# main.net
KiCad netlist of a schematic drawn in EAGLE
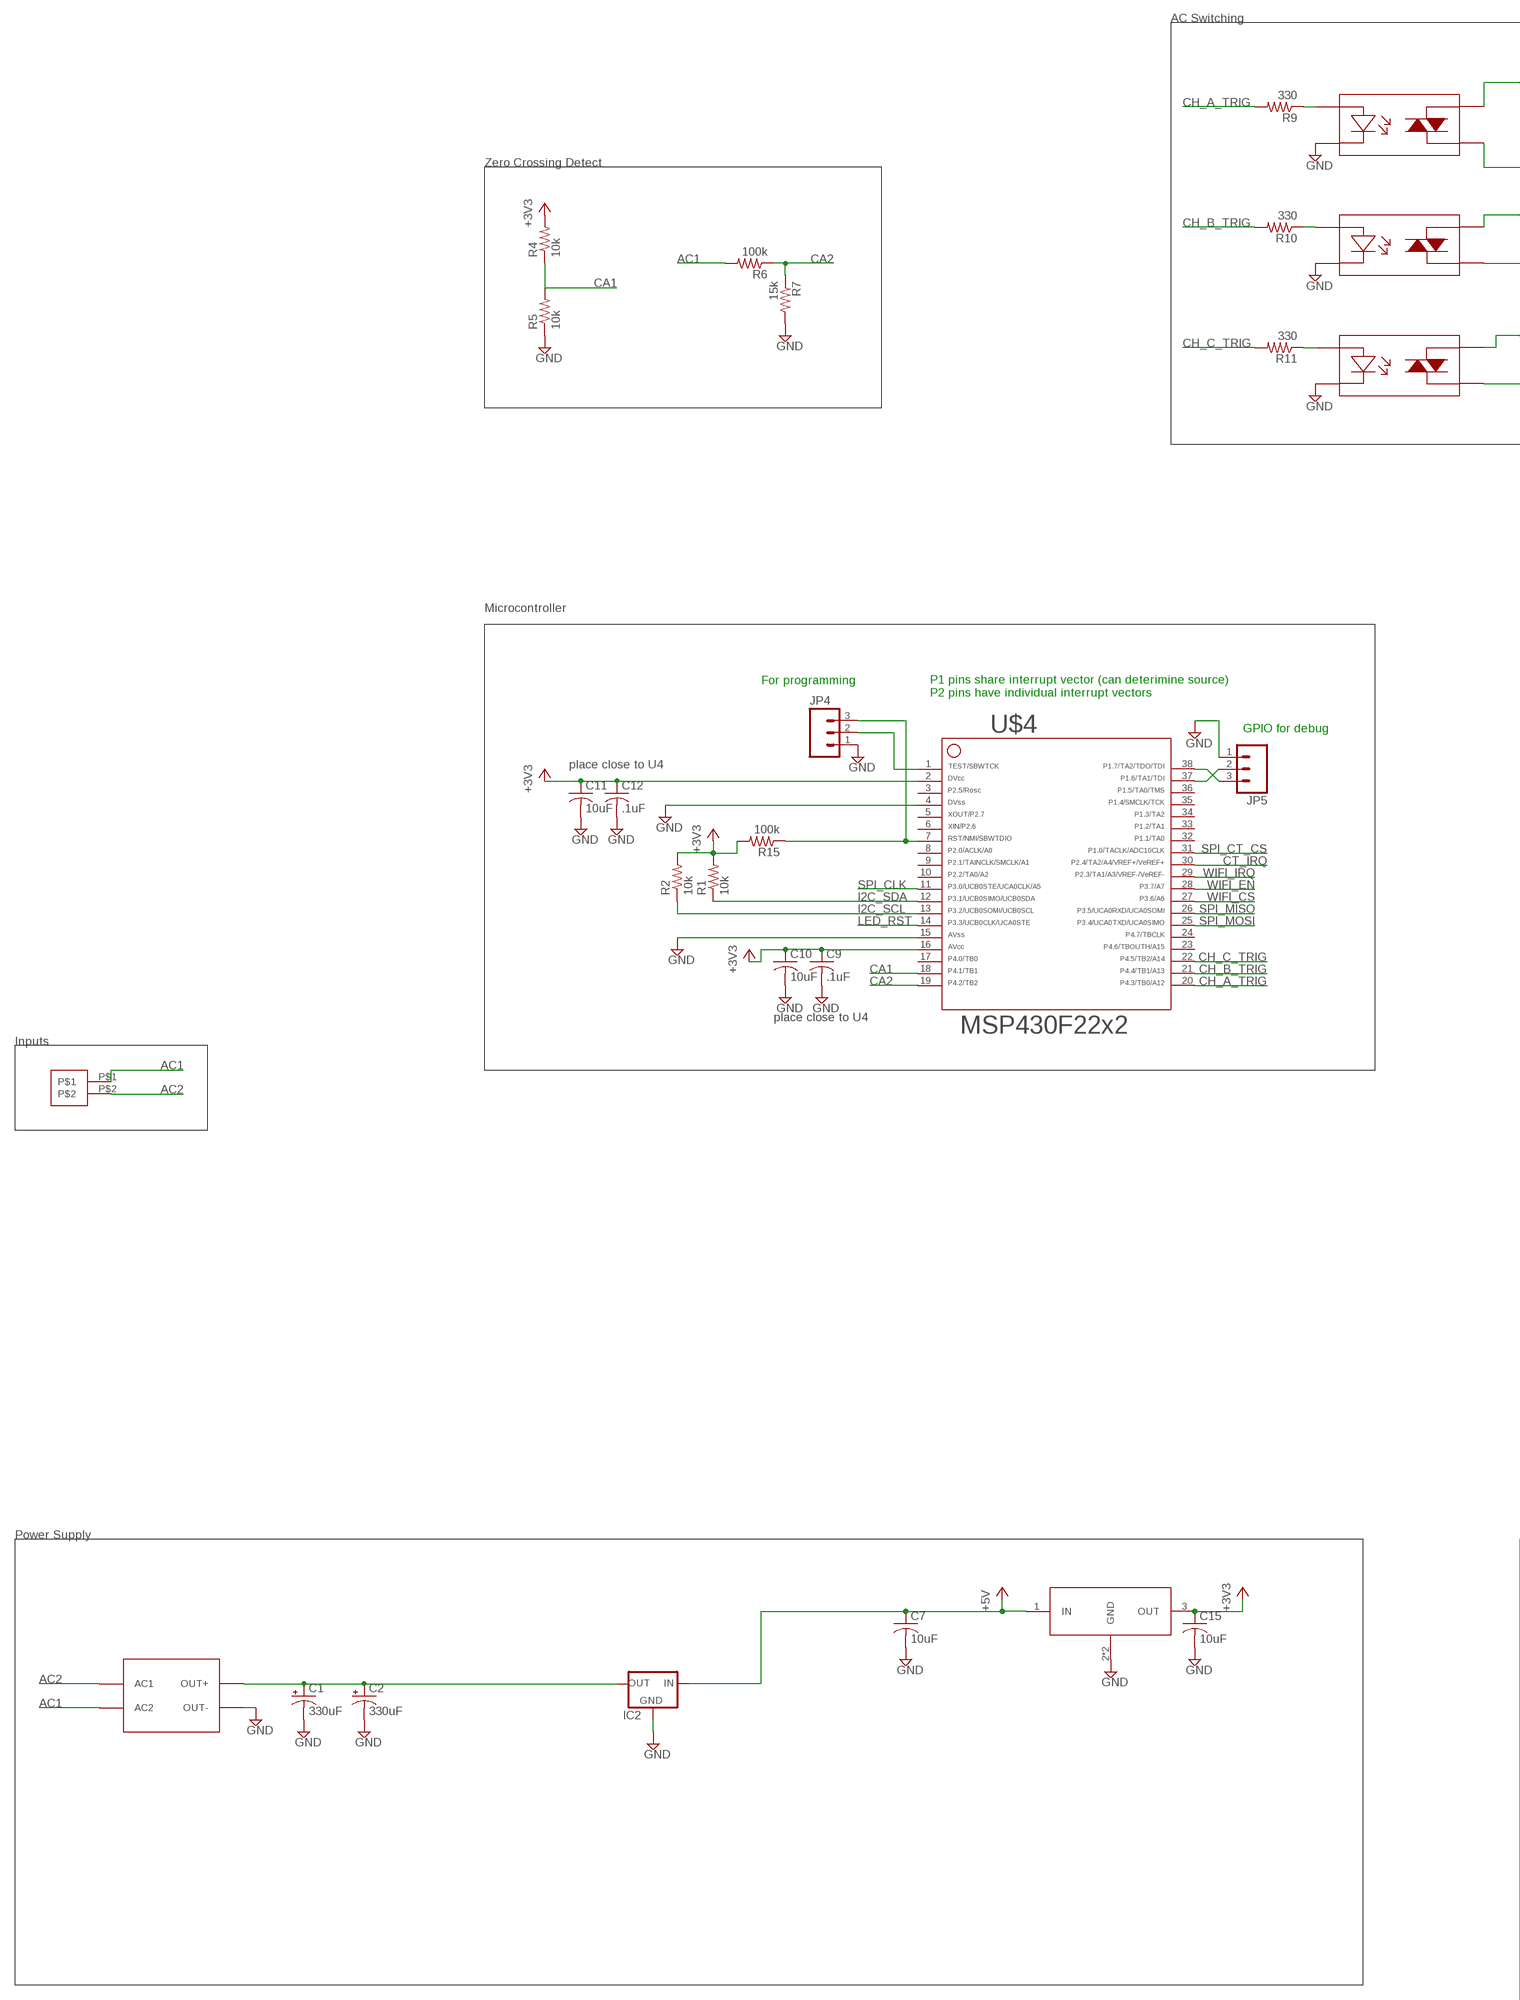
[diagram p0: schematic, sheet 1, part 1 of 2]
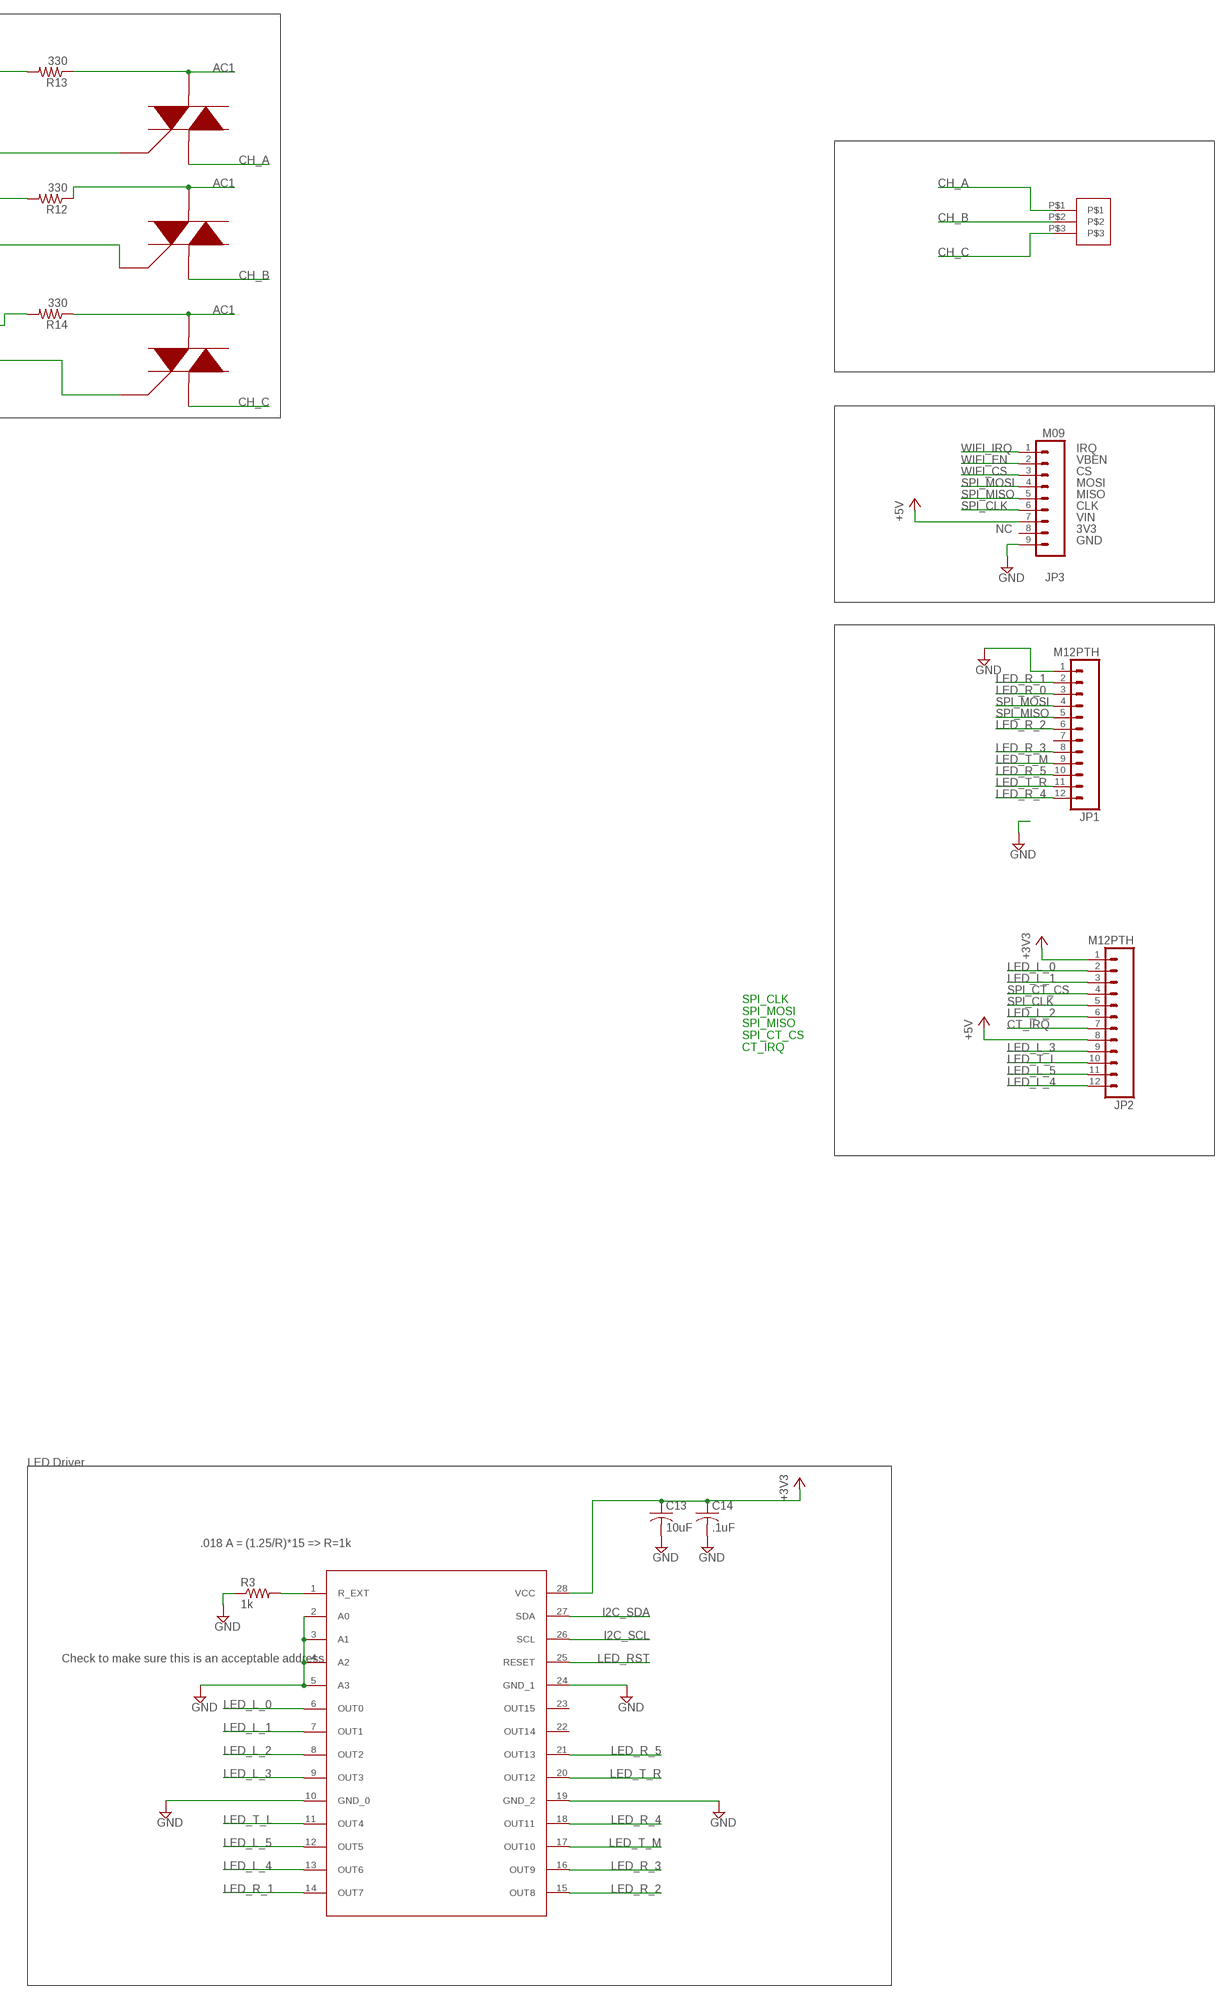
[diagram p1: schematic, sheet 1, part 2 of 2]

(export (version "E")
  (design (tool "Eeschema 10.0.6"))
  (components
    (comp (ref "C1")
      (value "330uF")
      (footprint "eagle-import:RADIAL_CAN_SMD")
      (libsource (lib "eagle-import") (part "EEE-1VA331UAP"))
    )
    (comp (ref "C2")
      (value "330uF")
      (footprint "eagle-import:RADIAL_CAN_SMD")
      (libsource (lib "eagle-import") (part "EEE-1VA331UAP"))
    )
    (comp (ref "C7")
      (value "10uF")
      (footprint "eagle-import:C0603K")
      (libsource (lib "eagle-import") (part "C-USC0603K"))
    )
    (comp (ref "C9")
      (value ".1uF")
      (footprint "eagle-import:C0603K")
      (libsource (lib "eagle-import") (part "C-USC0603K"))
    )
    (comp (ref "C10")
      (value "10uF")
      (footprint "eagle-import:C0603K")
      (libsource (lib "eagle-import") (part "C-USC0603K"))
    )
    (comp (ref "C11")
      (value "10uF")
      (footprint "eagle-import:C0603K")
      (libsource (lib "eagle-import") (part "C-USC0603K"))
    )
    (comp (ref "C12")
      (value ".1uF")
      (footprint "eagle-import:C0603K")
      (libsource (lib "eagle-import") (part "C-USC0603K"))
    )
    (comp (ref "C13")
      (value "10uF")
      (footprint "eagle-import:C0603K")
      (libsource (lib "eagle-import") (part "C-USC0603K"))
    )
    (comp (ref "C14")
      (value ".1uF")
      (footprint "eagle-import:C0603K")
      (libsource (lib "eagle-import") (part "C-USC0603K"))
    )
    (comp (ref "C15")
      (value "10uF")
      (footprint "eagle-import:C0603K")
      (libsource (lib "eagle-import") (part "C-USC0603K"))
    )
    (comp (ref "IC2")
      (value "V_REG_78XX-TO-220")
      (footprint "eagle-import:TO-220-ALT")
      (libsource (lib "eagle-import") (part "V_REG_78XX-TO-220"))
    )
    (comp (ref "J1")
      (value "3-1437646-3")
      (footprint "eagle-import:3-1437646-3")
      (libsource (lib "eagle-import") (part "3-1437646-3"))
    )
    (comp (ref "J2")
      (value "3-1437646-9")
      (footprint "eagle-import:3-1437646-9")
      (libsource (lib "eagle-import") (part "3-1437646-9"))
    )
    (comp (ref "JP1")
      (value "M12PTH")
      (footprint "eagle-import:1X12")
      (libsource (lib "eagle-import") (part "M12PTH"))
    )
    (comp (ref "JP2")
      (value "M12PTH")
      (footprint "eagle-import:1X12")
      (libsource (lib "eagle-import") (part "M12PTH"))
    )
    (comp (ref "JP3")
      (value "M09")
      (footprint "eagle-import:1X09")
      (libsource (lib "eagle-import") (part "M09"))
    )
    (comp (ref "JP4")
      (value "M03PTH")
      (footprint "eagle-import:1X03")
      (libsource (lib "eagle-import") (part "M03PTH"))
    )
    (comp (ref "JP5")
      (value "M03PTH")
      (footprint "eagle-import:1X03")
      (libsource (lib "eagle-import") (part "M03PTH"))
    )
    (comp (ref "R1")
      (value "10k")
      (footprint "eagle-import:R0603")
      (libsource (lib "eagle-import") (part "R-US_R0603"))
    )
    (comp (ref "R2")
      (value "10k")
      (footprint "eagle-import:R0603")
      (libsource (lib "eagle-import") (part "R-US_R0603"))
    )
    (comp (ref "R3")
      (value "1k")
      (footprint "eagle-import:R0603")
      (libsource (lib "eagle-import") (part "R-US_R0603"))
    )
    (comp (ref "R4")
      (value "10k")
      (footprint "eagle-import:R0603")
      (libsource (lib "eagle-import") (part "R-US_R0603"))
    )
    (comp (ref "R5")
      (value "10k")
      (footprint "eagle-import:R0603")
      (libsource (lib "eagle-import") (part "R-US_R0603"))
    )
    (comp (ref "R6")
      (value "100k")
      (footprint "eagle-import:R0603")
      (libsource (lib "eagle-import") (part "R-US_R0603"))
    )
    (comp (ref "R7")
      (value "15k")
      (footprint "eagle-import:R0603")
      (libsource (lib "eagle-import") (part "R-US_R0603"))
    )
    (comp (ref "R9")
      (value "330")
      (footprint "eagle-import:R0603")
      (libsource (lib "eagle-import") (part "R-US_R0603"))
    )
    (comp (ref "R10")
      (value "330")
      (footprint "eagle-import:R0603")
      (libsource (lib "eagle-import") (part "R-US_R0603"))
    )
    (comp (ref "R11")
      (value "330")
      (footprint "eagle-import:R0603")
      (libsource (lib "eagle-import") (part "R-US_R0603"))
    )
    (comp (ref "R12")
      (value "330")
      (footprint "eagle-import:R0603")
      (libsource (lib "eagle-import") (part "R-US_R0603"))
    )
    (comp (ref "R13")
      (value "330")
      (footprint "eagle-import:R0603")
      (libsource (lib "eagle-import") (part "R-US_R0603"))
    )
    (comp (ref "R14")
      (value "330")
      (footprint "eagle-import:R0603")
      (libsource (lib "eagle-import") (part "R-US_R0603"))
    )
    (comp (ref "R15")
      (value "100k")
      (footprint "eagle-import:R0603")
      (libsource (lib "eagle-import") (part "R-US_R0603"))
    )
    (comp (ref "U$1")
      (value "FODM3011")
      (footprint "eagle-import:SMD-4")
      (libsource (lib "eagle-import") (part "FODM3011"))
    )
    (comp (ref "U$2")
      (value "DS1501S-T")
      (footprint "eagle-import:DF-S")
      (libsource (lib "eagle-import") (part "DS1501S-T"))
    )
    (comp (ref "U$3")
      (value "TLC59116")
      (footprint "eagle-import:PW_28")
      (libsource (lib "eagle-import") (part "TLC59116"))
    )
    (comp (ref "U$4")
      (value "F22X2---DA38")
      (footprint "eagle-import:DA38")
      (libsource (lib "eagle-import") (part "F22X2---DA38"))
    )
    (comp (ref "U$5")
      (value "LM2937")
      (footprint "eagle-import:SOT223")
      (libsource (lib "eagle-import") (part "LM2937"))
    )
    (comp (ref "U$6")
      (value "FODM3011")
      (footprint "eagle-import:SMD-4")
      (libsource (lib "eagle-import") (part "FODM3011"))
    )
    (comp (ref "U$7")
      (value "FODM3011")
      (footprint "eagle-import:SMD-4")
      (libsource (lib "eagle-import") (part "FODM3011"))
    )
    (comp (ref "U$9")
      (value "BT-137S-600D")
      (footprint "eagle-import:SOT428")
      (libsource (lib "eagle-import") (part "BT-137S-600D"))
    )
    (comp (ref "U$10")
      (value "BT-137S-600D")
      (footprint "eagle-import:SOT428")
      (libsource (lib "eagle-import") (part "BT-137S-600D"))
    )
    (comp (ref "U$11")
      (value "BT-137S-600D")
      (footprint "eagle-import:SOT428")
      (libsource (lib "eagle-import") (part "BT-137S-600D"))
    )
  )
  (nets
    (net (code "1") (name "+3V3") (class "Default")
      (node (ref "C10") (pin "1") (pinfunction "1_1") (pintype "passive"))
      (node (ref "C11") (pin "1") (pinfunction "1_1") (pintype "passive"))
      (node (ref "C12") (pin "1") (pinfunction "1_1") (pintype "passive"))
      (node (ref "C13") (pin "1") (pinfunction "1_1") (pintype "passive"))
      (node (ref "C14") (pin "1") (pinfunction "1_1") (pintype "passive"))
      (node (ref "C15") (pin "1") (pinfunction "1_1") (pintype "passive"))
      (node (ref "C9") (pin "1") (pinfunction "1_1") (pintype "passive"))
      (node (ref "JP2") (pin "1") (pinfunction "1_1") (pintype "passive"))
      (node (ref "R1") (pin "2") (pinfunction "2_2") (pintype "passive"))
      (node (ref "R15") (pin "2") (pinfunction "2_2") (pintype "passive"))
      (node (ref "R2") (pin "2") (pinfunction "2_2") (pintype "passive"))
      (node (ref "R4") (pin "2") (pinfunction "2_2") (pintype "passive"))
      (node (ref "U$3") (pin "28") (pinfunction "VCC_28") (pintype "bidirectional"))
      (node (ref "U$4") (pin "16") (pinfunction "16_16") (pintype "power_in"))
      (node (ref "U$4") (pin "2") (pinfunction "2_2") (pintype "power_in"))
      (node (ref "U$5") (pin "3") (pinfunction "OUT_3") (pintype "bidirectional"))
    )
    (net (code "2") (name "+5V") (class "Default")
      (node (ref "C7") (pin "1") (pinfunction "1_1") (pintype "passive"))
      (node (ref "IC2") (pin "IN") (pinfunction "IN_IN") (pintype "input"))
      (node (ref "JP2") (pin "8") (pinfunction "8_8") (pintype "passive"))
      (node (ref "JP3") (pin "7") (pinfunction "7_7") (pintype "passive"))
      (node (ref "U$5") (pin "1") (pinfunction "IN_1") (pintype "bidirectional"))
    )
    (net (code "3") (name "/AC1") (class "Default")
      (node (ref "J1") (pin "P$1") (pinfunction "P$1_P$1") (pintype "bidirectional"))
      (node (ref "R12") (pin "1") (pinfunction "1_1") (pintype "passive"))
      (node (ref "R13") (pin "1") (pinfunction "1_1") (pintype "passive"))
      (node (ref "R14") (pin "1") (pinfunction "1_1") (pintype "passive"))
      (node (ref "R6") (pin "2") (pinfunction "2_2") (pintype "passive"))
      (node (ref "U$10") (pin "T2") (pinfunction "S2_T2") (pintype "bidirectional"))
      (node (ref "U$11") (pin "T2") (pinfunction "S2_T2") (pintype "bidirectional"))
      (node (ref "U$2") (pin "P$4") (pinfunction "AC2_P$4") (pintype "bidirectional"))
      (node (ref "U$9") (pin "T2") (pinfunction "S2_T2") (pintype "bidirectional"))
    )
    (net (code "4") (name "/AC2") (class "Default")
      (node (ref "J1") (pin "P$2") (pinfunction "P$2_P$2") (pintype "bidirectional"))
      (node (ref "U$2") (pin "P$3") (pinfunction "AC1_P$3") (pintype "bidirectional"))
    )
    (net (code "5") (name "/CA1") (class "Default")
      (node (ref "R4") (pin "1") (pinfunction "1_1") (pintype "passive"))
      (node (ref "R5") (pin "2") (pinfunction "2_2") (pintype "passive"))
      (node (ref "U$4") (pin "18") (pinfunction "18_18") (pintype "bidirectional"))
    )
    (net (code "6") (name "/CA2") (class "Default")
      (node (ref "R6") (pin "1") (pinfunction "1_1") (pintype "passive"))
      (node (ref "R7") (pin "1") (pinfunction "1_1") (pintype "passive"))
      (node (ref "U$4") (pin "19") (pinfunction "19_19") (pintype "bidirectional"))
    )
    (net (code "7") (name "/CH_A") (class "Default")
      (node (ref "J2") (pin "P$1") (pinfunction "P$1_P$1") (pintype "bidirectional"))
      (node (ref "U$9") (pin "T1") (pinfunction "S1_T1") (pintype "bidirectional"))
    )
    (net (code "8") (name "/CH_A_TRIG") (class "Default")
      (node (ref "R9") (pin "2") (pinfunction "2_2") (pintype "passive"))
      (node (ref "U$4") (pin "20") (pinfunction "20_20") (pintype "bidirectional"))
    )
    (net (code "9") (name "/CH_B") (class "Default")
      (node (ref "J2") (pin "P$2") (pinfunction "P$2_P$2") (pintype "bidirectional"))
      (node (ref "U$10") (pin "T1") (pinfunction "S1_T1") (pintype "bidirectional"))
    )
    (net (code "10") (name "/CH_B_TRIG") (class "Default")
      (node (ref "R10") (pin "2") (pinfunction "2_2") (pintype "passive"))
      (node (ref "U$4") (pin "21") (pinfunction "21_21") (pintype "bidirectional"))
    )
    (net (code "11") (name "/CH_C") (class "Default")
      (node (ref "J2") (pin "P$3") (pinfunction "P$3_P$3") (pintype "bidirectional"))
      (node (ref "U$11") (pin "T1") (pinfunction "S1_T1") (pintype "bidirectional"))
    )
    (net (code "12") (name "/CH_C_TRIG") (class "Default")
      (node (ref "R11") (pin "2") (pinfunction "2_2") (pintype "passive"))
      (node (ref "U$4") (pin "22") (pinfunction "22_22") (pintype "bidirectional"))
    )
    (net (code "13") (name "/CT_IRQ") (class "Default")
      (node (ref "JP2") (pin "7") (pinfunction "7_7") (pintype "passive"))
      (node (ref "U$4") (pin "30") (pinfunction "30_30") (pintype "bidirectional"))
    )
    (net (code "14") (name "/I2C_SCL") (class "Default")
      (node (ref "R2") (pin "1") (pinfunction "1_1") (pintype "passive"))
      (node (ref "U$3") (pin "26") (pinfunction "SCL_26") (pintype "bidirectional"))
      (node (ref "U$4") (pin "13") (pinfunction "13_13") (pintype "bidirectional"))
    )
    (net (code "15") (name "/I2C_SDA") (class "Default")
      (node (ref "R1") (pin "1") (pinfunction "1_1") (pintype "passive"))
      (node (ref "U$3") (pin "27") (pinfunction "SDA_27") (pintype "bidirectional"))
      (node (ref "U$4") (pin "12") (pinfunction "12_12") (pintype "bidirectional"))
    )
    (net (code "16") (name "/LED_L_0") (class "Default")
      (node (ref "JP2") (pin "2") (pinfunction "2_2") (pintype "passive"))
      (node (ref "U$3") (pin "6") (pinfunction "OUT0_6") (pintype "bidirectional"))
    )
    (net (code "17") (name "/LED_L_1") (class "Default")
      (node (ref "JP2") (pin "3") (pinfunction "3_3") (pintype "passive"))
      (node (ref "U$3") (pin "7") (pinfunction "OUT1_7") (pintype "bidirectional"))
    )
    (net (code "18") (name "/LED_L_2") (class "Default")
      (node (ref "JP2") (pin "6") (pinfunction "6_6") (pintype "passive"))
      (node (ref "U$3") (pin "8") (pinfunction "OUT2_8") (pintype "bidirectional"))
    )
    (net (code "19") (name "/LED_L_3") (class "Default")
      (node (ref "JP2") (pin "9") (pinfunction "9_9") (pintype "passive"))
      (node (ref "U$3") (pin "9") (pinfunction "OUT3_9") (pintype "bidirectional"))
    )
    (net (code "20") (name "/LED_L_4") (class "Default")
      (node (ref "JP2") (pin "12") (pinfunction "12_12") (pintype "passive"))
      (node (ref "U$3") (pin "13") (pinfunction "OUT6_13") (pintype "bidirectional"))
    )
    (net (code "21") (name "/LED_L_5") (class "Default")
      (node (ref "JP2") (pin "11") (pinfunction "11_11") (pintype "passive"))
      (node (ref "U$3") (pin "12") (pinfunction "OUT5_12") (pintype "bidirectional"))
    )
    (net (code "22") (name "/LED_RST") (class "Default")
      (node (ref "U$3") (pin "25") (pinfunction "RESET_25") (pintype "bidirectional"))
      (node (ref "U$4") (pin "14") (pinfunction "14_14") (pintype "bidirectional"))
    )
    (net (code "23") (name "/LED_R_0") (class "Default")
      (node (ref "JP1") (pin "3") (pinfunction "3_3") (pintype "passive"))
    )
    (net (code "24") (name "/LED_R_1") (class "Default")
      (node (ref "JP1") (pin "2") (pinfunction "2_2") (pintype "passive"))
      (node (ref "U$3") (pin "14") (pinfunction "OUT7_14") (pintype "bidirectional"))
    )
    (net (code "25") (name "/LED_R_2") (class "Default")
      (node (ref "JP1") (pin "6") (pinfunction "6_6") (pintype "passive"))
      (node (ref "U$3") (pin "15") (pinfunction "OUT8_15") (pintype "bidirectional"))
    )
    (net (code "26") (name "/LED_R_3") (class "Default")
      (node (ref "JP1") (pin "8") (pinfunction "8_8") (pintype "passive"))
      (node (ref "U$3") (pin "16") (pinfunction "OUT9_16") (pintype "bidirectional"))
    )
    (net (code "27") (name "/LED_R_4") (class "Default")
      (node (ref "JP1") (pin "12") (pinfunction "12_12") (pintype "passive"))
      (node (ref "U$3") (pin "18") (pinfunction "OUT11_18") (pintype "bidirectional"))
    )
    (net (code "28") (name "/LED_R_5") (class "Default")
      (node (ref "JP1") (pin "10") (pinfunction "10_10") (pintype "passive"))
      (node (ref "U$3") (pin "21") (pinfunction "OUT13_21") (pintype "bidirectional"))
    )
    (net (code "29") (name "/LED_T_L") (class "Default")
      (node (ref "JP2") (pin "10") (pinfunction "10_10") (pintype "passive"))
      (node (ref "U$3") (pin "11") (pinfunction "OUT4_11") (pintype "bidirectional"))
    )
    (net (code "30") (name "/LED_T_M") (class "Default")
      (node (ref "JP1") (pin "9") (pinfunction "9_9") (pintype "passive"))
      (node (ref "U$3") (pin "17") (pinfunction "OUT10_17") (pintype "bidirectional"))
    )
    (net (code "31") (name "/LED_T_R") (class "Default")
      (node (ref "JP1") (pin "11") (pinfunction "11_11") (pintype "passive"))
      (node (ref "U$3") (pin "20") (pinfunction "OUT12_20") (pintype "bidirectional"))
    )
    (net (code "32") (name "/SPI_CLK") (class "Default")
      (node (ref "JP2") (pin "5") (pinfunction "5_5") (pintype "passive"))
      (node (ref "JP3") (pin "6") (pinfunction "6_6") (pintype "passive"))
      (node (ref "U$4") (pin "11") (pinfunction "11_11") (pintype "bidirectional"))
    )
    (net (code "33") (name "/SPI_CT_CS") (class "Default")
      (node (ref "JP2") (pin "4") (pinfunction "4_4") (pintype "passive"))
      (node (ref "U$4") (pin "31") (pinfunction "31_31") (pintype "bidirectional"))
    )
    (net (code "34") (name "/SPI_MISO") (class "Default")
      (node (ref "JP1") (pin "5") (pinfunction "5_5") (pintype "passive"))
      (node (ref "JP3") (pin "5") (pinfunction "5_5") (pintype "passive"))
      (node (ref "U$4") (pin "26") (pinfunction "26_26") (pintype "bidirectional"))
    )
    (net (code "35") (name "/SPI_MOSI") (class "Default")
      (node (ref "JP1") (pin "4") (pinfunction "4_4") (pintype "passive"))
      (node (ref "JP3") (pin "4") (pinfunction "4_4") (pintype "passive"))
      (node (ref "U$4") (pin "25") (pinfunction "25_25") (pintype "bidirectional"))
    )
    (net (code "36") (name "/WIFI_CS") (class "Default")
      (node (ref "JP3") (pin "3") (pinfunction "3_3") (pintype "passive"))
      (node (ref "U$4") (pin "27") (pinfunction "27_27") (pintype "bidirectional"))
    )
    (net (code "37") (name "/WIFI_EN") (class "Default")
      (node (ref "JP3") (pin "2") (pinfunction "2_2") (pintype "passive"))
      (node (ref "U$4") (pin "28") (pinfunction "28_28") (pintype "bidirectional"))
    )
    (net (code "38") (name "/WIFI_IRQ") (class "Default")
      (node (ref "JP3") (pin "1") (pinfunction "1_1") (pintype "passive"))
      (node (ref "U$4") (pin "29") (pinfunction "29_29") (pintype "bidirectional"))
    )
    (net (code "39") (name "GND") (class "Default")
      (node (ref "C1") (pin "-") (pinfunction "-_-") (pintype "passive"))
      (node (ref "C10") (pin "2") (pinfunction "2_2") (pintype "passive"))
      (node (ref "C11") (pin "2") (pinfunction "2_2") (pintype "passive"))
      (node (ref "C12") (pin "2") (pinfunction "2_2") (pintype "passive"))
      (node (ref "C13") (pin "2") (pinfunction "2_2") (pintype "passive"))
      (node (ref "C14") (pin "2") (pinfunction "2_2") (pintype "passive"))
      (node (ref "C15") (pin "2") (pinfunction "2_2") (pintype "passive"))
      (node (ref "C2") (pin "-") (pinfunction "-_-") (pintype "passive"))
      (node (ref "C7") (pin "2") (pinfunction "2_2") (pintype "passive"))
      (node (ref "C9") (pin "2") (pinfunction "2_2") (pintype "passive"))
      (node (ref "IC2") (pin "GND") (pinfunction "GND_GND") (pintype "input"))
      (node (ref "JP1") (pin "1") (pinfunction "1_1") (pintype "passive"))
      (node (ref "JP3") (pin "9") (pinfunction "9_9") (pintype "passive"))
      (node (ref "JP4") (pin "1") (pinfunction "1_1") (pintype "passive"))
      (node (ref "JP5") (pin "1") (pinfunction "1_1") (pintype "passive"))
      (node (ref "R3") (pin "1") (pinfunction "1_1") (pintype "passive"))
      (node (ref "R5") (pin "1") (pinfunction "1_1") (pintype "passive"))
      (node (ref "R7") (pin "2") (pinfunction "2_2") (pintype "passive"))
      (node (ref "U$1") (pin "P$2") (pinfunction "LED-_P$2") (pintype "bidirectional"))
      (node (ref "U$2") (pin "P$2") (pinfunction "OUT-_P$2") (pintype "bidirectional"))
      (node (ref "U$3") (pin "10") (pinfunction "GND_0_10") (pintype "bidirectional"))
      (node (ref "U$3") (pin "19") (pinfunction "GND_2_19") (pintype "bidirectional"))
      (node (ref "U$3") (pin "2") (pinfunction "A0_2") (pintype "bidirectional"))
      (node (ref "U$3") (pin "24") (pinfunction "GND_1_24") (pintype "bidirectional"))
      (node (ref "U$3") (pin "3") (pinfunction "A1_3") (pintype "bidirectional"))
      (node (ref "U$3") (pin "4") (pinfunction "A2_4") (pintype "bidirectional"))
      (node (ref "U$3") (pin "5") (pinfunction "A3_5") (pintype "bidirectional"))
      (node (ref "U$4") (pin "15") (pinfunction "15_15") (pintype "power_in"))
      (node (ref "U$4") (pin "4") (pinfunction "4_4") (pintype "power_in"))
      (node (ref "U$5") (pin "2") (pinfunction "GND_2") (pintype "bidirectional"))
      (node (ref "U$5") (pin "4") (pinfunction "GND_4") (pintype "bidirectional"))
      (node (ref "U$6") (pin "P$2") (pinfunction "LED-_P$2") (pintype "bidirectional"))
      (node (ref "U$7") (pin "P$2") (pinfunction "LED-_P$2") (pintype "bidirectional"))
    )
    (net (code "40") (name "Net-(JP4-Pad2)") (class "Default")
      (node (ref "JP4") (pin "2") (pinfunction "2_2") (pintype "passive"))
      (node (ref "U$4") (pin "1") (pinfunction "1_1") (pintype "input"))
    )
    (net (code "41") (name "Net-(JP4-Pad3)") (class "Default")
      (node (ref "JP4") (pin "3") (pinfunction "3_3") (pintype "passive"))
      (node (ref "R15") (pin "1") (pinfunction "1_1") (pintype "passive"))
      (node (ref "U$4") (pin "7") (pinfunction "7_7") (pintype "bidirectional"))
    )
    (net (code "42") (name "Net-(JP5-Pad2)") (class "Default")
      (node (ref "JP5") (pin "2") (pinfunction "2_2") (pintype "passive"))
      (node (ref "U$4") (pin "37") (pinfunction "37_37") (pintype "bidirectional"))
    )
    (net (code "43") (name "Net-(JP5-Pad3)") (class "Default")
      (node (ref "JP5") (pin "3") (pinfunction "3_3") (pintype "passive"))
      (node (ref "U$4") (pin "38") (pinfunction "38_38") (pintype "bidirectional"))
    )
    (net (code "44") (name "Net-(U$1-LED+)") (class "Default")
      (node (ref "R9") (pin "1") (pinfunction "1_1") (pintype "passive"))
      (node (ref "U$1") (pin "P$1") (pinfunction "LED+_P$1") (pintype "bidirectional"))
    )
    (net (code "45") (name "Net-(U$1-S1)") (class "Default")
      (node (ref "R13") (pin "2") (pinfunction "2_2") (pintype "passive"))
      (node (ref "U$1") (pin "P$3") (pinfunction "S1_P$3") (pintype "bidirectional"))
    )
    (net (code "46") (name "Net-(U$1-S2)") (class "Default")
      (node (ref "U$1") (pin "P$4") (pinfunction "S2_P$4") (pintype "bidirectional"))
      (node (ref "U$9") (pin "G") (pinfunction "G_G") (pintype "bidirectional"))
    )
    (net (code "47") (name "Net-(U$2-OUT+)") (class "Default")
      (node (ref "C1") (pin "+") (pinfunction "+_+") (pintype "passive"))
      (node (ref "C2") (pin "+") (pinfunction "+_+") (pintype "passive"))
      (node (ref "IC2") (pin "OUT") (pinfunction "OUT_OUT") (pintype "output"))
      (node (ref "U$2") (pin "P$1") (pinfunction "OUT+_P$1") (pintype "bidirectional"))
    )
    (net (code "48") (name "Net-(U$3-R_EXT)") (class "Default")
      (node (ref "R3") (pin "2") (pinfunction "2_2") (pintype "passive"))
      (node (ref "U$3") (pin "1") (pinfunction "R_EXT_1") (pintype "bidirectional"))
    )
    (net (code "49") (name "Net-(U$6-LED+)") (class "Default")
      (node (ref "R10") (pin "1") (pinfunction "1_1") (pintype "passive"))
      (node (ref "U$6") (pin "P$1") (pinfunction "LED+_P$1") (pintype "bidirectional"))
    )
    (net (code "50") (name "Net-(U$6-S1)") (class "Default")
      (node (ref "R12") (pin "2") (pinfunction "2_2") (pintype "passive"))
      (node (ref "U$6") (pin "P$3") (pinfunction "S1_P$3") (pintype "bidirectional"))
    )
    (net (code "51") (name "Net-(U$6-S2)") (class "Default")
      (node (ref "U$10") (pin "G") (pinfunction "G_G") (pintype "bidirectional"))
      (node (ref "U$6") (pin "P$4") (pinfunction "S2_P$4") (pintype "bidirectional"))
    )
    (net (code "52") (name "Net-(U$7-LED+)") (class "Default")
      (node (ref "R11") (pin "1") (pinfunction "1_1") (pintype "passive"))
      (node (ref "U$7") (pin "P$1") (pinfunction "LED+_P$1") (pintype "bidirectional"))
    )
    (net (code "53") (name "Net-(U$7-S1)") (class "Default")
      (node (ref "R14") (pin "2") (pinfunction "2_2") (pintype "passive"))
      (node (ref "U$7") (pin "P$3") (pinfunction "S1_P$3") (pintype "bidirectional"))
    )
    (net (code "54") (name "Net-(U$7-S2)") (class "Default")
      (node (ref "U$11") (pin "G") (pinfunction "G_G") (pintype "bidirectional"))
      (node (ref "U$7") (pin "P$4") (pinfunction "S2_P$4") (pintype "bidirectional"))
    )
    (net (code "55") (name "unconnected-(JP1-Pad7)") (class "Default")
      (node (ref "JP1") (pin "7") (pinfunction "7_7") (pintype "passive"))
    )
    (net (code "56") (name "unconnected-(JP3-Pad8)") (class "Default")
      (node (ref "JP3") (pin "8") (pinfunction "8_8") (pintype "passive"))
    )
    (net (code "57") (name "unconnected-(U$3-OUT14-Pad22)") (class "Default")
      (node (ref "U$3") (pin "22") (pinfunction "OUT14_22") (pintype "bidirectional"))
    )
    (net (code "58") (name "unconnected-(U$3-OUT15-Pad23)") (class "Default")
      (node (ref "U$3") (pin "23") (pinfunction "OUT15_23") (pintype "bidirectional"))
    )
    (net (code "59") (name "unconnected-(U$4-Pad3)") (class "Default")
      (node (ref "U$4") (pin "3") (pinfunction "3_3") (pintype "bidirectional"))
    )
    (net (code "60") (name "unconnected-(U$4-Pad5)") (class "Default")
      (node (ref "U$4") (pin "5") (pinfunction "5_5") (pintype "bidirectional"))
    )
    (net (code "61") (name "unconnected-(U$4-Pad6)") (class "Default")
      (node (ref "U$4") (pin "6") (pinfunction "6_6") (pintype "bidirectional"))
    )
    (net (code "62") (name "unconnected-(U$4-Pad8)") (class "Default")
      (node (ref "U$4") (pin "8") (pinfunction "8_8") (pintype "bidirectional"))
    )
    (net (code "63") (name "unconnected-(U$4-Pad9)") (class "Default")
      (node (ref "U$4") (pin "9") (pinfunction "9_9") (pintype "bidirectional"))
    )
    (net (code "64") (name "unconnected-(U$4-Pad10)") (class "Default")
      (node (ref "U$4") (pin "10") (pinfunction "10_10") (pintype "bidirectional"))
    )
    (net (code "65") (name "unconnected-(U$4-Pad17)") (class "Default")
      (node (ref "U$4") (pin "17") (pinfunction "17_17") (pintype "bidirectional"))
    )
    (net (code "66") (name "unconnected-(U$4-Pad23)") (class "Default")
      (node (ref "U$4") (pin "23") (pinfunction "23_23") (pintype "bidirectional"))
    )
    (net (code "67") (name "unconnected-(U$4-Pad24)") (class "Default")
      (node (ref "U$4") (pin "24") (pinfunction "24_24") (pintype "bidirectional"))
    )
    (net (code "68") (name "unconnected-(U$4-Pad32)") (class "Default")
      (node (ref "U$4") (pin "32") (pinfunction "32_32") (pintype "bidirectional"))
    )
    (net (code "69") (name "unconnected-(U$4-Pad33)") (class "Default")
      (node (ref "U$4") (pin "33") (pinfunction "33_33") (pintype "bidirectional"))
    )
    (net (code "70") (name "unconnected-(U$4-Pad34)") (class "Default")
      (node (ref "U$4") (pin "34") (pinfunction "34_34") (pintype "bidirectional"))
    )
    (net (code "71") (name "unconnected-(U$4-Pad35)") (class "Default")
      (node (ref "U$4") (pin "35") (pinfunction "35_35") (pintype "bidirectional"))
    )
    (net (code "72") (name "unconnected-(U$4-Pad36)") (class "Default")
      (node (ref "U$4") (pin "36") (pinfunction "36_36") (pintype "bidirectional"))
    )
  )
)
